# 1v8_Regulator.net
KiCad netlist of a schematic drawn in Altium Designer
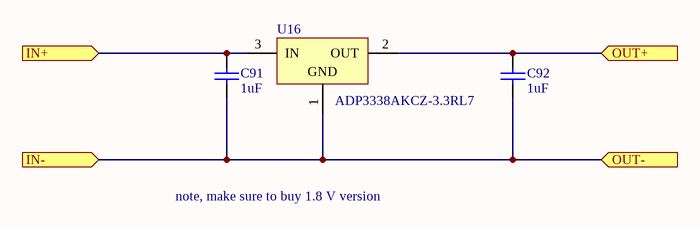
[diagram p0: 1v8_Regulator.SchDoc]

(export (version "E")
  (design (tool "Eeschema 10.0.6"))
  (components
    (comp (ref "C91")
      (value "1uF")
      (footprint "0402_Cap")
      (description "Capacitor, 1uF, 0805")
      (libsource (lib "Arturo_Approved") (part "CL21B105KBFNFNE"))
    )
    (comp (ref "C92")
      (value "1uF")
      (footprint "0402_Cap")
      (description "Capacitor, 1uF, 0805")
      (libsource (lib "Arturo_Approved") (part "CL21B105KBFNFNE"))
    )
    (comp (ref "U16")
      (value "ADP3338AKCZ-3.3RL7")
      (footprint "ADI-KC-3_M")
      (fields (field (name "MANUFACTURER") "Analog Devices"))
      (libsource (lib "Altium Content Vault") (part "ADI-ADP3338-KC-3"))
    )
  )
  (nets
    (net (code "1") (name "/IN+") (class "Default")
      (node (ref "C91") (pin "2") (pinfunction "2_2") (pintype "passive"))
      (node (ref "U16") (pin "3") (pinfunction "IN_3") (pintype "power_in"))
    )
    (net (code "2") (name "/IN-") (class "Default")
      (node (ref "C91") (pin "1") (pinfunction "1_1") (pintype "passive"))
      (node (ref "C92") (pin "1") (pinfunction "1_1") (pintype "passive"))
      (node (ref "U16") (pin "1") (pinfunction "GND_1") (pintype "power_in"))
    )
    (net (code "3") (name "/OUT+") (class "Default")
      (node (ref "C92") (pin "2") (pinfunction "2_2") (pintype "passive"))
      (node (ref "U16") (pin "2") (pinfunction "OUT_2") (pintype "power_in"))
    )
  )
)
